# Sch_RoverLite_v1.net
KiCad netlist of a schematic drawn in Altium Designer
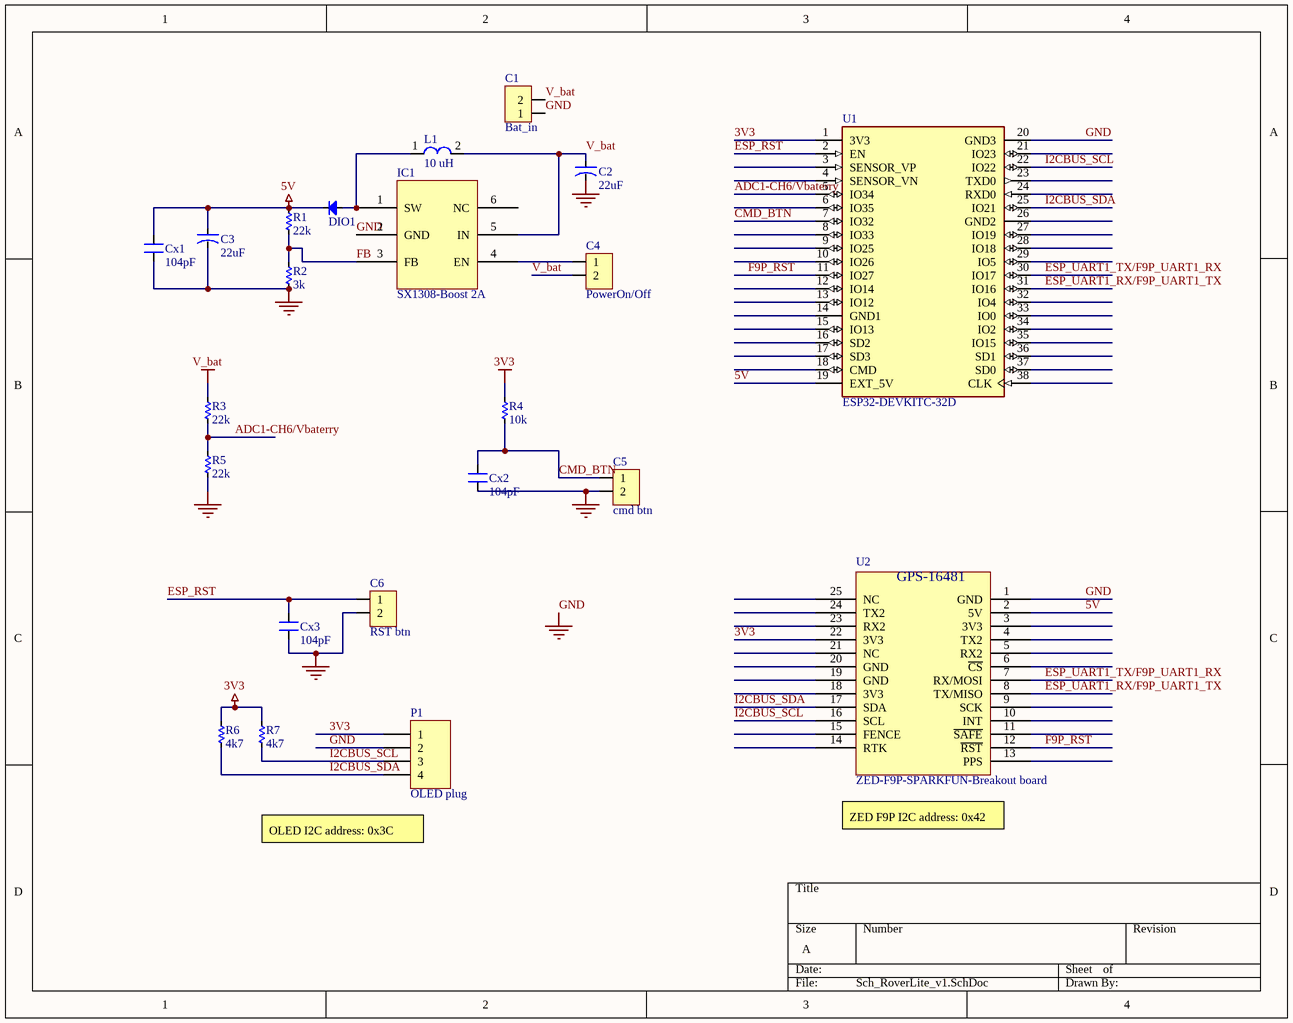
[diagram p0: Sch_RoverLite_v1.SchDoc]

(export (version "E")
  (design (tool "Eeschema 10.0.6"))
  (components
    (comp (ref "C1")
      (value "Bat_in")
      (footprint "HDR2")
      (description "Header IDC, 2 x 1 Pin Vertical 2.54mm Pitch (Non-Boxed, Male)")
      (fields
        (field (name "MANUFACTURER") "Würth Elektronik eiSos GmbH")
        (field (name "PARTNO") "613002143121")
        (field (name "CREATED BY") "Karrer Zheng")
      )
      (libsource (lib "") (part "Header2_1"))
    )
    (comp (ref "C2")
      (value "22uF")
      (footprint "CAP-ALU-SMD-6.3x7.7x2.2")
      (description "Polarized Capacitor (Axial)")
      (fields (field (name "PUBLISHER") "Altium Limited"))
      (libsource (lib "TechMT.VN_Lib_Project v2") (part "CN-ALU-SMD"))
    )
    (comp (ref "C3")
      (value "22uF")
      (footprint "CAP-ALU-SMD-6.3x7.7x2.2")
      (description "Polarized Capacitor (Axial)")
      (fields (field (name "PUBLISHER") "Altium Limited"))
      (libsource (lib "TechMT.VN_Lib_Project v2") (part "CN-ALU-SMD"))
    )
    (comp (ref "C4")
      (value "PowerOn/Off")
      (footprint "HDR2")
      (description "Header IDC, 2 x 1 Pin Vertical 2.54mm Pitch (Non-Boxed, Male)")
      (fields
        (field (name "MANUFACTURER") "Würth Elektronik eiSos GmbH")
        (field (name "PARTNO") "613002143121")
        (field (name "CREATED BY") "Karrer Zheng")
      )
      (libsource (lib "TechMT.VN_Lib_Project v2") (part "Header2"))
    )
    (comp (ref "C5")
      (value "cmd btn")
      (footprint "HDR2")
      (description "Header IDC, 2 x 1 Pin Vertical 2.54mm Pitch (Non-Boxed, Male)")
      (fields
        (field (name "MANUFACTURER") "Würth Elektronik eiSos GmbH")
        (field (name "PARTNO") "613002143121")
        (field (name "CREATED BY") "Karrer Zheng")
      )
      (libsource (lib "TechMT.VN_Lib_Project v2") (part "Header2"))
    )
    (comp (ref "C6")
      (value "RST btn")
      (footprint "HDR2")
      (description "Header IDC, 2 x 1 Pin Vertical 2.54mm Pitch (Non-Boxed, Male)")
      (fields
        (field (name "MANUFACTURER") "Würth Elektronik eiSos GmbH")
        (field (name "PARTNO") "613002143121")
        (field (name "CREATED BY") "Karrer Zheng")
      )
      (libsource (lib "TechMT.VN_Lib_Project v2") (part "Header2"))
    )
    (comp (ref "Cx1")
      (value "104pF")
      (footprint "CN-SMD-1206")
      (libsource (lib "TechMT.VN_Lib_Project v2") (part "CN"))
    )
    (comp (ref "Cx2")
      (value "104pF")
      (footprint "CN-SMD-0805")
      (libsource (lib "TechMT.VN_Lib_Project v2") (part "CN"))
    )
    (comp (ref "Cx3")
      (value "104pF")
      (footprint "CN-SMD-0805")
      (libsource (lib "TechMT.VN_Lib_Project v2") (part "CN"))
    )
    (comp (ref "DIO1")
      (value "SS34")
      (footprint "DIO-SMD-216AA")
      (description "Default Diode")
      (fields (field (name "PUBLISHER") "Altium Limited"))
      (libsource (lib "TechMT.VN_Lib_Project v2") (part "Diode SMD"))
    )
    (comp (ref "IC1")
      (value "SX1308-Boost 2A")
      (footprint "SX1308fpt")
      (libsource (lib "Rover_lite_Lib") (part "SX1308-Boost 2A"))
    )
    (comp (ref "L1")
      (value "10 uH")
      (footprint "L-SMD-M-7.3x4.5")
      (fields
        (field (name "PARTNO") "78477010")
        (field (name "MANUFACTURER") "Wurth Elektronik")
        (field (name "CREATED BY") "Baojun Chen")
      )
      (libsource (lib "TechMT.VN_Lib_Project v2") (part "L-SMD-1"))
    )
    (comp (ref "P1")
      (value "OLED plug")
      (footprint "HDR1X4")
      (description "Header, 4-Pin")
      (fields (field (name "PUBLISHER") "Altium Limited"))
      (libsource (lib "Miscellaneous Connectors") (part "Header 4"))
    )
    (comp (ref "R1")
      (value "22k")
      (footprint "RES-SMD-0805")
      (description "Resistor")
      (fields
        (field (name "MANUFACTURER") "Generic Components")
        (field (name "PUBLISHER") "Altium Hobart Technology Centre")
      )
      (libsource (lib "TechMT.VN_Lib_Project v2") (part "Res-SMD"))
    )
    (comp (ref "R2")
      (value "3k")
      (footprint "RES-SMD-0805")
      (description "Resistor")
      (fields
        (field (name "MANUFACTURER") "Generic Components")
        (field (name "PUBLISHER") "Altium Hobart Technology Centre")
      )
      (libsource (lib "TechMT.VN_Lib_Project v2") (part "Res-SMD"))
    )
    (comp (ref "R3")
      (value "22k")
      (footprint "RES-SMD-0805")
      (description "Resistor")
      (fields
        (field (name "MANUFACTURER") "Generic Components")
        (field (name "PUBLISHER") "Altium Hobart Technology Centre")
      )
      (libsource (lib "TechMT.VN_Lib_Project v2") (part "Res-SMD"))
    )
    (comp (ref "R4")
      (value "10k")
      (footprint "RES-SMD-0805")
      (description "Resistor")
      (fields
        (field (name "MANUFACTURER") "Generic Components")
        (field (name "PUBLISHER") "Altium Hobart Technology Centre")
      )
      (libsource (lib "TechMT.VN_Lib_Project v2") (part "Res-SMD"))
    )
    (comp (ref "R5")
      (value "22k")
      (footprint "RES-SMD-0805")
      (description "Resistor")
      (fields
        (field (name "MANUFACTURER") "Generic Components")
        (field (name "PUBLISHER") "Altium Hobart Technology Centre")
      )
      (libsource (lib "TechMT.VN_Lib_Project v2") (part "Res-SMD"))
    )
    (comp (ref "R6")
      (value "4k7")
      (footprint "RES-SMD-0805")
      (description "Resistor")
      (fields
        (field (name "MANUFACTURER") "Generic Components")
        (field (name "PUBLISHER") "Altium Hobart Technology Centre")
      )
      (libsource (lib "TechMT.VN_Lib_Project v2") (part "Res-SMD"))
    )
    (comp (ref "R7")
      (value "4k7")
      (footprint "RES-SMD-0805")
      (description "Resistor")
      (fields
        (field (name "MANUFACTURER") "Generic Components")
        (field (name "PUBLISHER") "Altium Hobart Technology Centre")
      )
      (libsource (lib "TechMT.VN_Lib_Project v2") (part "Res-SMD"))
    )
    (comp (ref "U1")
      (value "ESP32-DEVKITC-32D")
      (footprint "MODULE_ESP32-DEVKITC-32D")
      (description "EVAL BOARD FOR ESP-WROOM-32")
      (fields (field (name "MF") "Espressif Systems"))
      (libsource (lib "Rover_lite_Lib") (part "ESP32-DEVKITC-32D"))
    )
    (comp (ref "U2")
      (value "ZED-F9P-SPARKFUN-Breakout board")
      (footprint "GPS-16481")
      (libsource (lib "Rover_lite_Lib") (part "ZED-F9P-SPARKFUN-Breakout board"))
    )
  )
  (nets
    (net (code "1") (name "/ADC1-CH6{slash}Vbaterry") (class "Default")
      (node (ref "R3") (pin "2") (pinfunction "2_2") (pintype "passive"))
      (node (ref "R5") (pin "1") (pinfunction "1_1") (pintype "passive"))
      (node (ref "U1") (pin "5") (pinfunction "IO34_5") (pintype "bidirectional"))
    )
    (net (code "2") (name "/CMD_BTN") (class "Default")
      (node (ref "C5") (pin "1") (pinfunction "1_1") (pintype "passive"))
      (node (ref "Cx2") (pin "2") (pinfunction "2_2") (pintype "passive"))
      (node (ref "R4") (pin "2") (pinfunction "2_2") (pintype "passive"))
      (node (ref "U1") (pin "7") (pinfunction "IO32_7") (pintype "bidirectional"))
    )
    (net (code "3") (name "/ESP_RST") (class "Default")
      (node (ref "C6") (pin "1") (pinfunction "1_1") (pintype "passive"))
      (node (ref "Cx3") (pin "2") (pinfunction "2_2") (pintype "passive"))
      (node (ref "U1") (pin "2") (pinfunction "EN_2") (pintype "input"))
    )
    (net (code "4") (name "/ESP_UART1_RX{slash}F9P_UART1_TX") (class "Default")
      (node (ref "U1") (pin "31") (pinfunction "IO16_31") (pintype "bidirectional"))
      (node (ref "U2") (pin "8") (pinfunction "TX/MISO_8") (pintype "passive"))
    )
    (net (code "5") (name "/ESP_UART1_TX{slash}F9P_UART1_RX") (class "Default")
      (node (ref "U1") (pin "30") (pinfunction "IO17_30") (pintype "bidirectional"))
      (node (ref "U2") (pin "7") (pinfunction "RX/MOSI_7") (pintype "passive"))
    )
    (net (code "6") (name "/F9P_RST") (class "Default")
      (node (ref "U1") (pin "11") (pinfunction "IO27_11") (pintype "bidirectional"))
      (node (ref "U2") (pin "12") (pinfunction "~{RST}_12") (pintype "passive"))
    )
    (net (code "7") (name "/FB") (class "Default")
      (node (ref "IC1") (pin "3") (pinfunction "FB_3") (pintype "passive"))
      (node (ref "R1") (pin "2") (pinfunction "2_2") (pintype "passive"))
      (node (ref "R2") (pin "1") (pinfunction "1_1") (pintype "passive"))
    )
    (net (code "8") (name "/GND") (class "Default")
      (node (ref "C1") (pin "1") (pinfunction "1_1") (pintype "passive"))
      (node (ref "C2") (pin "2") (pinfunction "2_2") (pintype "passive"))
      (node (ref "C3") (pin "2") (pinfunction "2_2") (pintype "passive"))
      (node (ref "C5") (pin "2") (pinfunction "2_2") (pintype "passive"))
      (node (ref "C6") (pin "2") (pinfunction "2_2") (pintype "passive"))
      (node (ref "Cx1") (pin "1") (pinfunction "1_1") (pintype "passive"))
      (node (ref "Cx2") (pin "1") (pinfunction "1_1") (pintype "passive"))
      (node (ref "Cx3") (pin "1") (pinfunction "1_1") (pintype "passive"))
      (node (ref "IC1") (pin "2") (pinfunction "GND_2") (pintype "passive"))
      (node (ref "P1") (pin "2") (pinfunction "2_2") (pintype "passive"))
      (node (ref "R2") (pin "2") (pinfunction "2_2") (pintype "passive"))
      (node (ref "R5") (pin "2") (pinfunction "2_2") (pintype "passive"))
      (node (ref "U1") (pin "20") (pinfunction "GND3_20") (pintype "power_in"))
      (node (ref "U2") (pin "1") (pinfunction "GND_1") (pintype "passive"))
    )
    (net (code "9") (name "/I2CBUS_SCL") (class "Default")
      (node (ref "P1") (pin "3") (pinfunction "3_3") (pintype "passive"))
      (node (ref "R7") (pin "2") (pinfunction "2_2") (pintype "passive"))
      (node (ref "U1") (pin "22") (pinfunction "IO22_22") (pintype "bidirectional"))
      (node (ref "U2") (pin "16") (pinfunction "SCL_16") (pintype "passive"))
    )
    (net (code "10") (name "/I2CBUS_SDA") (class "Default")
      (node (ref "P1") (pin "4") (pinfunction "4_4") (pintype "passive"))
      (node (ref "R6") (pin "2") (pinfunction "2_2") (pintype "passive"))
      (node (ref "U1") (pin "25") (pinfunction "IO21_25") (pintype "bidirectional"))
      (node (ref "U2") (pin "17") (pinfunction "SDA_17") (pintype "passive"))
    )
    (net (code "11") (name "3V3") (class "Default")
      (node (ref "P1") (pin "1") (pinfunction "1_1") (pintype "passive"))
      (node (ref "R4") (pin "1") (pinfunction "1_1") (pintype "passive"))
      (node (ref "R6") (pin "1") (pinfunction "1_1") (pintype "passive"))
      (node (ref "R7") (pin "1") (pinfunction "1_1") (pintype "passive"))
      (node (ref "U1") (pin "1") (pinfunction "3V3_1") (pintype "power_in"))
      (node (ref "U2") (pin "22") (pinfunction "3V3_22") (pintype "passive"))
    )
    (net (code "12") (name "5V") (class "Default")
      (node (ref "C3") (pin "1") (pinfunction "1_1") (pintype "passive"))
      (node (ref "Cx1") (pin "2") (pinfunction "2_2") (pintype "passive"))
      (node (ref "DIO1") (pin "2") (pinfunction "K_2") (pintype "passive"))
      (node (ref "R1") (pin "1") (pinfunction "1_1") (pintype "passive"))
      (node (ref "U1") (pin "19") (pinfunction "EXT_5V_19") (pintype "power_in"))
      (node (ref "U2") (pin "2") (pinfunction "5V_2") (pintype "passive"))
    )
    (net (code "13") (name "Net-(DIO1-A)") (class "Default")
      (node (ref "DIO1") (pin "1") (pinfunction "A_1") (pintype "passive"))
      (node (ref "IC1") (pin "1") (pinfunction "SW_1") (pintype "passive"))
      (node (ref "L1") (pin "1") (pinfunction "1_1") (pintype "passive"))
    )
    (net (code "14") (name "Net-(IC1-EN)") (class "Default")
      (node (ref "C4") (pin "1") (pinfunction "1_1") (pintype "passive"))
      (node (ref "IC1") (pin "4") (pinfunction "EN_4") (pintype "passive"))
    )
    (net (code "15") (name "V_bat") (class "Default")
      (node (ref "C1") (pin "2") (pinfunction "2_2") (pintype "passive"))
      (node (ref "C2") (pin "1") (pinfunction "1_1") (pintype "passive"))
      (node (ref "C4") (pin "2") (pinfunction "2_2") (pintype "passive"))
      (node (ref "IC1") (pin "5") (pinfunction "IN_5") (pintype "passive"))
      (node (ref "L1") (pin "2") (pinfunction "2_2") (pintype "passive"))
      (node (ref "R3") (pin "1") (pinfunction "1_1") (pintype "passive"))
    )
    (net (code "16") (name "unconnected-(IC1-NC-Pad6)") (class "Default")
      (node (ref "IC1") (pin "6") (pinfunction "NC_6") (pintype "passive"))
    )
    (net (code "17") (name "unconnected-(U1-CLK-Pad38)") (class "Default")
      (node (ref "U1") (pin "38") (pinfunction "CLK_38") (pintype "input"))
    )
    (net (code "18") (name "unconnected-(U1-CMD-Pad18)") (class "Default")
      (node (ref "U1") (pin "18") (pinfunction "CMD_18") (pintype "bidirectional"))
    )
    (net (code "19") (name "unconnected-(U1-GND1-Pad14)") (class "Default")
      (node (ref "U1") (pin "14") (pinfunction "GND1_14") (pintype "power_in"))
    )
    (net (code "20") (name "unconnected-(U1-GND2-Pad26)") (class "Default")
      (node (ref "U1") (pin "26") (pinfunction "GND2_26") (pintype "power_in"))
    )
    (net (code "21") (name "unconnected-(U1-IO0-Pad33)") (class "Default")
      (node (ref "U1") (pin "33") (pinfunction "IO0_33") (pintype "bidirectional"))
    )
    (net (code "22") (name "unconnected-(U1-IO2-Pad34)") (class "Default")
      (node (ref "U1") (pin "34") (pinfunction "IO2_34") (pintype "bidirectional"))
    )
    (net (code "23") (name "unconnected-(U1-IO4-Pad32)") (class "Default")
      (node (ref "U1") (pin "32") (pinfunction "IO4_32") (pintype "bidirectional"))
    )
    (net (code "24") (name "unconnected-(U1-IO5-Pad29)") (class "Default")
      (node (ref "U1") (pin "29") (pinfunction "IO5_29") (pintype "bidirectional"))
    )
    (net (code "25") (name "unconnected-(U1-IO12-Pad13)") (class "Default")
      (node (ref "U1") (pin "13") (pinfunction "IO12_13") (pintype "bidirectional"))
    )
    (net (code "26") (name "unconnected-(U1-IO13-Pad15)") (class "Default")
      (node (ref "U1") (pin "15") (pinfunction "IO13_15") (pintype "bidirectional"))
    )
    (net (code "27") (name "unconnected-(U1-IO14-Pad12)") (class "Default")
      (node (ref "U1") (pin "12") (pinfunction "IO14_12") (pintype "bidirectional"))
    )
    (net (code "28") (name "unconnected-(U1-IO15-Pad35)") (class "Default")
      (node (ref "U1") (pin "35") (pinfunction "IO15_35") (pintype "bidirectional"))
    )
    (net (code "29") (name "unconnected-(U1-IO18-Pad28)") (class "Default")
      (node (ref "U1") (pin "28") (pinfunction "IO18_28") (pintype "bidirectional"))
    )
    (net (code "30") (name "unconnected-(U1-IO19-Pad27)") (class "Default")
      (node (ref "U1") (pin "27") (pinfunction "IO19_27") (pintype "bidirectional"))
    )
    (net (code "31") (name "unconnected-(U1-IO23-Pad21)") (class "Default")
      (node (ref "U1") (pin "21") (pinfunction "IO23_21") (pintype "bidirectional"))
    )
    (net (code "32") (name "unconnected-(U1-IO25-Pad9)") (class "Default")
      (node (ref "U1") (pin "9") (pinfunction "IO25_9") (pintype "bidirectional"))
    )
    (net (code "33") (name "unconnected-(U1-IO26-Pad10)") (class "Default")
      (node (ref "U1") (pin "10") (pinfunction "IO26_10") (pintype "bidirectional"))
    )
    (net (code "34") (name "unconnected-(U1-IO33-Pad8)") (class "Default")
      (node (ref "U1") (pin "8") (pinfunction "IO33_8") (pintype "bidirectional"))
    )
    (net (code "35") (name "unconnected-(U1-IO35-Pad6)") (class "Default")
      (node (ref "U1") (pin "6") (pinfunction "IO35_6") (pintype "bidirectional"))
    )
    (net (code "36") (name "unconnected-(U1-RXD0-Pad24)") (class "Default")
      (node (ref "U1") (pin "24") (pinfunction "RXD0_24") (pintype "input"))
    )
    (net (code "37") (name "unconnected-(U1-SD0-Pad37)") (class "Default")
      (node (ref "U1") (pin "37") (pinfunction "SD0_37") (pintype "bidirectional"))
    )
    (net (code "38") (name "unconnected-(U1-SD1-Pad36)") (class "Default")
      (node (ref "U1") (pin "36") (pinfunction "SD1_36") (pintype "bidirectional"))
    )
    (net (code "39") (name "unconnected-(U1-SD2-Pad16)") (class "Default")
      (node (ref "U1") (pin "16") (pinfunction "SD2_16") (pintype "bidirectional"))
    )
    (net (code "40") (name "unconnected-(U1-SD3-Pad17)") (class "Default")
      (node (ref "U1") (pin "17") (pinfunction "SD3_17") (pintype "bidirectional"))
    )
    (net (code "41") (name "unconnected-(U1-SENSOR_VN-Pad4)") (class "Default")
      (node (ref "U1") (pin "4") (pinfunction "SENSOR_VN_4") (pintype "input"))
    )
    (net (code "42") (name "unconnected-(U1-SENSOR_VP-Pad3)") (class "Default")
      (node (ref "U1") (pin "3") (pinfunction "SENSOR_VP_3") (pintype "input"))
    )
    (net (code "43") (name "unconnected-(U1-TXD0-Pad23)") (class "Default")
      (node (ref "U1") (pin "23") (pinfunction "TXD0_23") (pintype "output"))
    )
    (net (code "44") (name "unconnected-(U2-3V3-Pad3)") (class "Default")
      (node (ref "U2") (pin "3") (pinfunction "3V3_3") (pintype "passive"))
    )
    (net (code "45") (name "unconnected-(U2-3V3-Pad18)") (class "Default")
      (node (ref "U2") (pin "18") (pinfunction "3V3_18") (pintype "passive"))
    )
    (net (code "46") (name "unconnected-(U2-FENCE-Pad15)") (class "Default")
      (node (ref "U2") (pin "15") (pinfunction "FENCE_15") (pintype "passive"))
    )
    (net (code "47") (name "unconnected-(U2-GND-Pad19)") (class "Default")
      (node (ref "U2") (pin "19") (pinfunction "GND_19") (pintype "passive"))
    )
    (net (code "48") (name "unconnected-(U2-GND-Pad20)") (class "Default")
      (node (ref "U2") (pin "20") (pinfunction "GND_20") (pintype "passive"))
    )
    (net (code "49") (name "unconnected-(U2-INT-Pad10)") (class "Default")
      (node (ref "U2") (pin "10") (pinfunction "INT_10") (pintype "passive"))
    )
    (net (code "50") (name "unconnected-(U2-NC-Pad21)") (class "Default")
      (node (ref "U2") (pin "21") (pinfunction "NC_21") (pintype "passive"))
    )
    (net (code "51") (name "unconnected-(U2-NC-Pad25)") (class "Default")
      (node (ref "U2") (pin "25") (pinfunction "NC_25") (pintype "passive"))
    )
    (net (code "52") (name "unconnected-(U2-PPS-Pad13)") (class "Default")
      (node (ref "U2") (pin "13") (pinfunction "PPS_13") (pintype "passive"))
    )
    (net (code "53") (name "unconnected-(U2-RTK-Pad14)") (class "Default")
      (node (ref "U2") (pin "14") (pinfunction "RTK_14") (pintype "passive"))
    )
    (net (code "54") (name "unconnected-(U2-RX2-Pad5)") (class "Default")
      (node (ref "U2") (pin "5") (pinfunction "RX2_5") (pintype "passive"))
    )
    (net (code "55") (name "unconnected-(U2-RX2-Pad23)") (class "Default")
      (node (ref "U2") (pin "23") (pinfunction "RX2_23") (pintype "passive"))
    )
    (net (code "56") (name "unconnected-(U2-SCK-Pad9)") (class "Default")
      (node (ref "U2") (pin "9") (pinfunction "SCK_9") (pintype "passive"))
    )
    (net (code "57") (name "unconnected-(U2-TX2-Pad4)") (class "Default")
      (node (ref "U2") (pin "4") (pinfunction "TX2_4") (pintype "passive"))
    )
    (net (code "58") (name "unconnected-(U2-TX2-Pad24)") (class "Default")
      (node (ref "U2") (pin "24") (pinfunction "TX2_24") (pintype "passive"))
    )
    (net (code "59") (name "unconnected-(U2-~{CS}-Pad6)") (class "Default")
      (node (ref "U2") (pin "6") (pinfunction "~{CS}_6") (pintype "passive"))
    )
    (net (code "60") (name "unconnected-(U2-~{SAFE}-Pad11)") (class "Default")
      (node (ref "U2") (pin "11") (pinfunction "~{SAFE}_11") (pintype "passive"))
    )
  )
)
